# info-orbs.net
KiCad netlist of a schematic drawn in EasyEDA
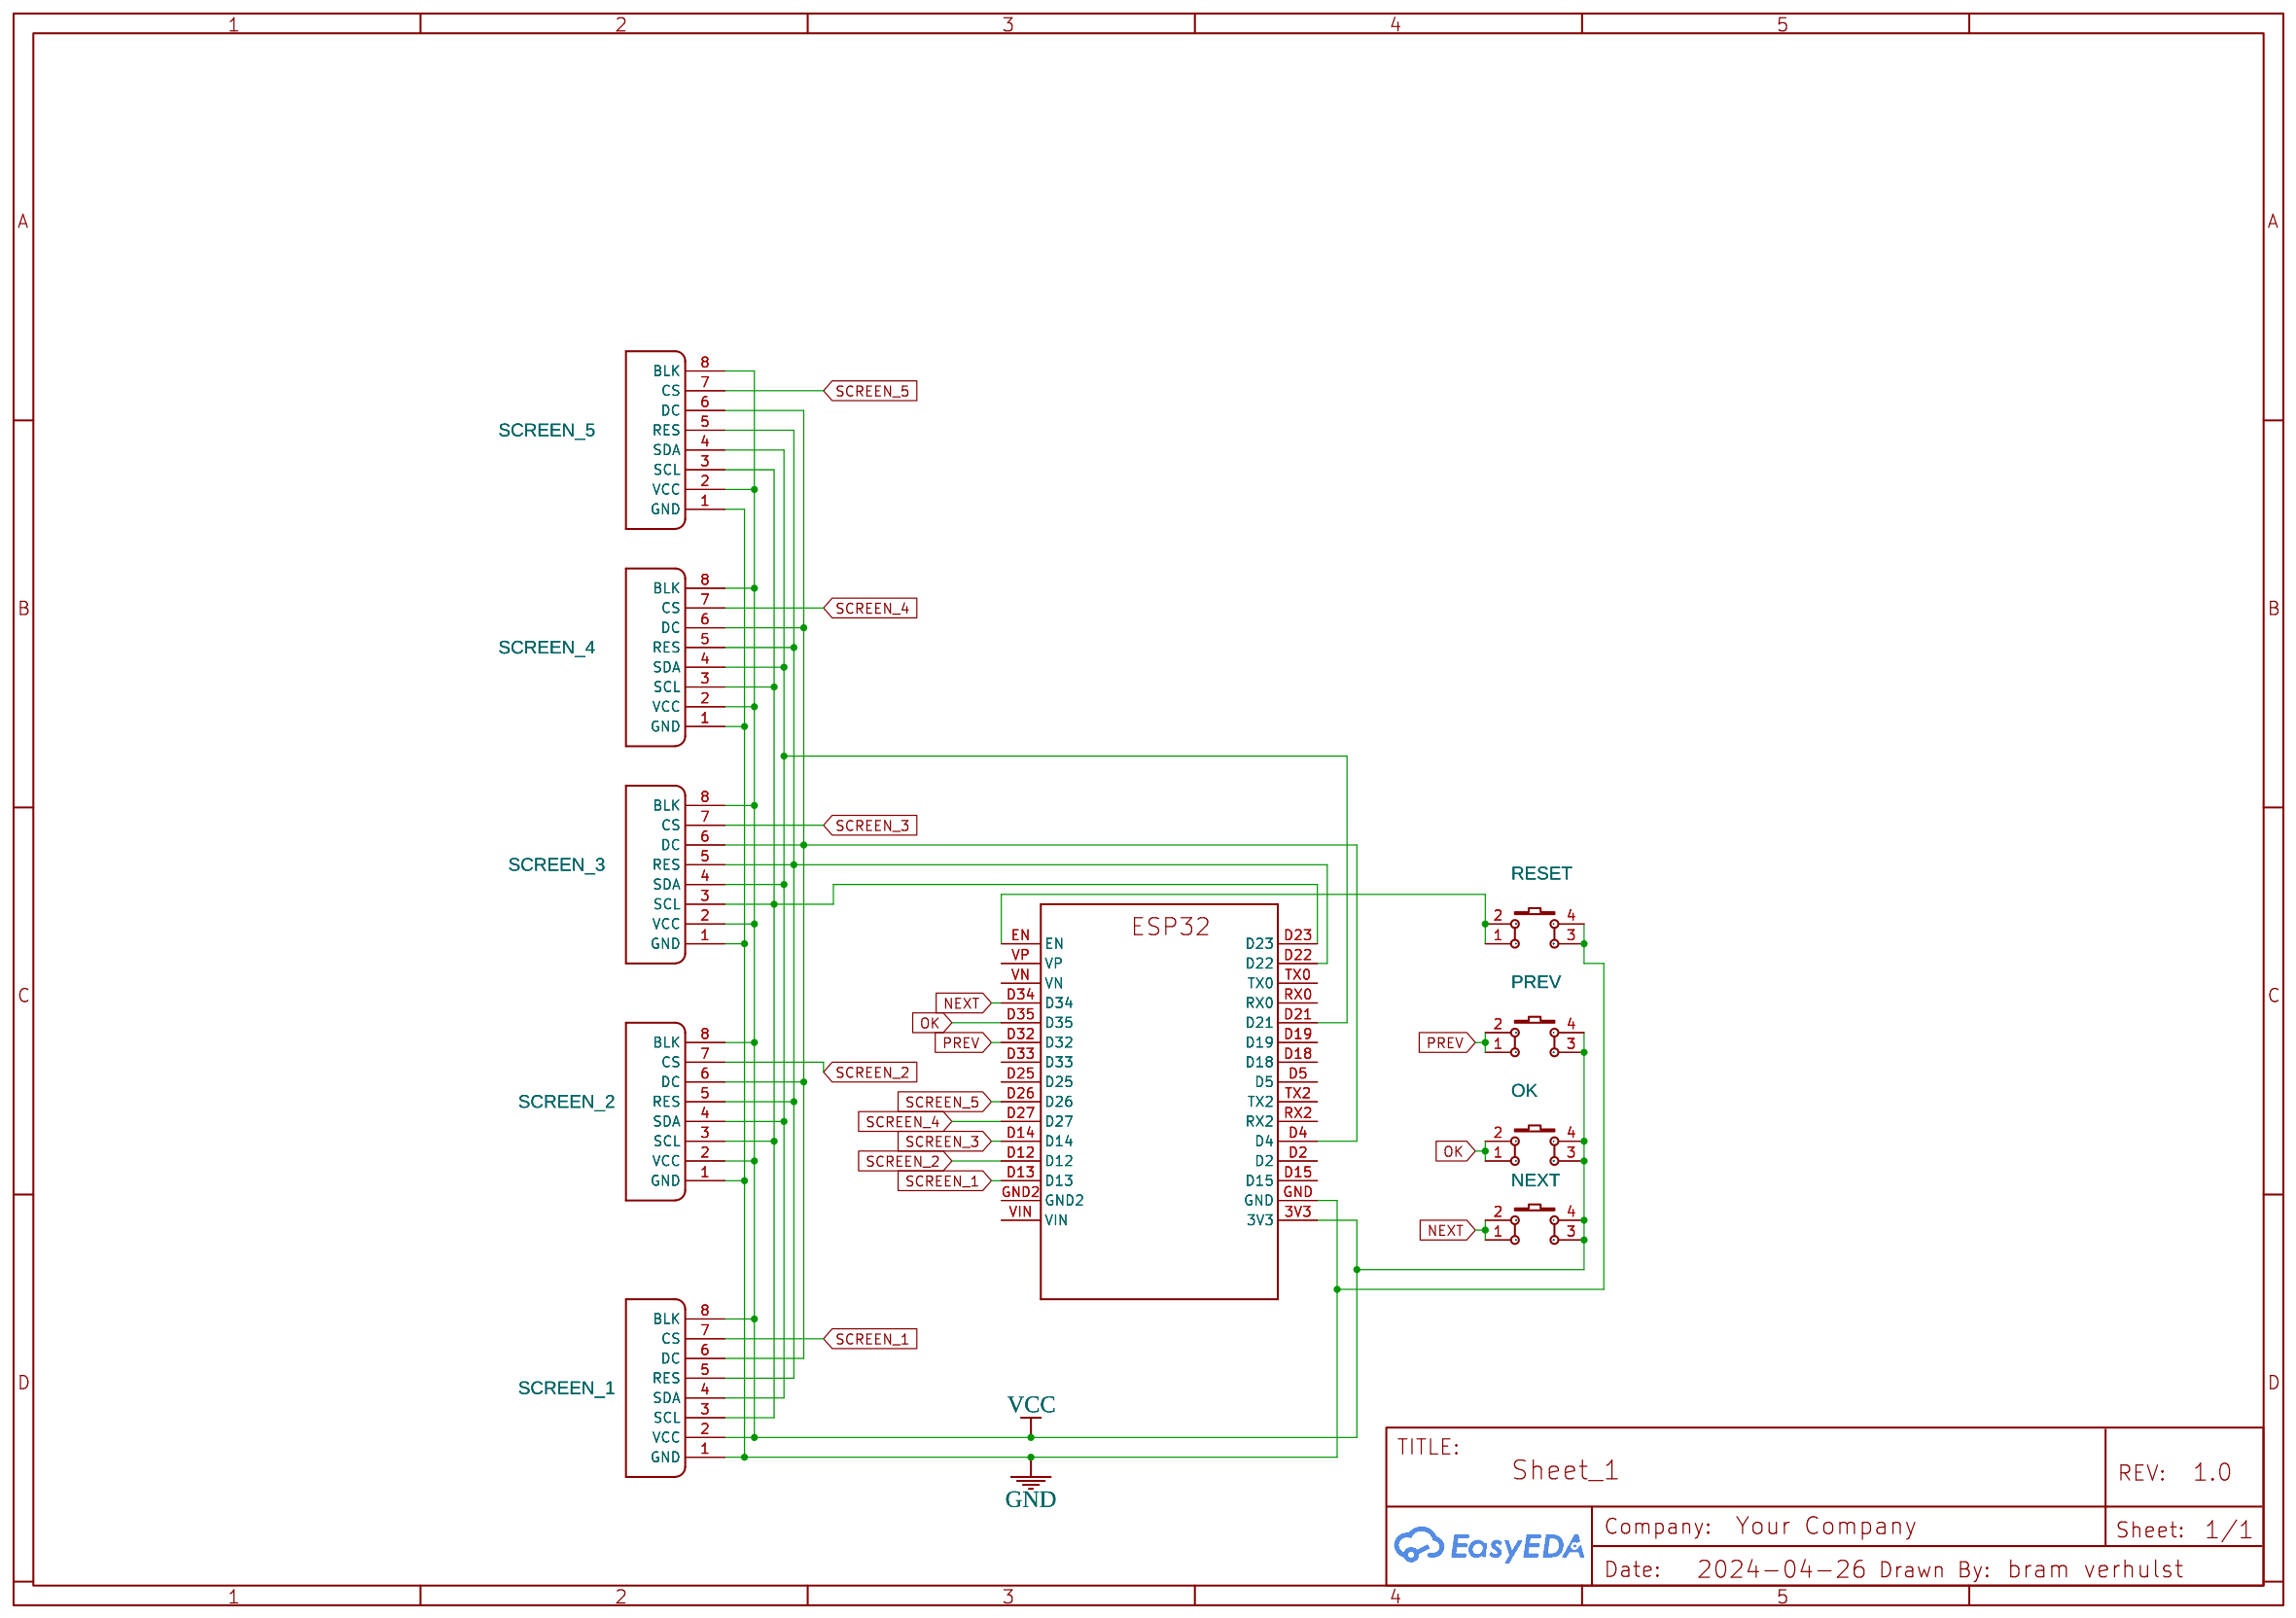
[diagram p0: schematic sheet]

(export (version "E")
  (design (tool "Eeschema 10.0.6"))
  (components
    (comp (ref "1")
      (value "ESP32-DEVKIT-V1-30PIN COPY 00.2 COPY")
      (libsource (lib "") (part "ESP32-DEVKIT-V1-30PIN"))
    )
    (comp (ref "NEXT")
      (value "K4-6×6_TH")
      (fields (field (name "Manufacturer Part") "K2-1102DP-E4SW-04") (field (name "Manufacturer") "韩国韩荣"))
      (libsource (lib "") (part "K4-6×6_TH"))
    )
    (comp (ref "OK")
      (value "K4-6×6_TH")
      (fields (field (name "Manufacturer Part") "K2-1102DP-E4SW-04") (field (name "Manufacturer") "韩国韩荣"))
      (libsource (lib "") (part "K4-6×6_TH_3"))
    )
    (comp (ref "PREV")
      (value "K4-6×6_TH")
      (fields (field (name "Manufacturer Part") "K2-1102DP-E4SW-04") (field (name "Manufacturer") "韩国韩荣"))
      (libsource (lib "") (part "K4-6×6_TH_1"))
    )
    (comp (ref "RESET")
      (value "K4-6×6_TH")
      (fields (field (name "Manufacturer Part") "K2-1102DP-E4SW-04") (field (name "Manufacturer") "韩国韩荣"))
      (libsource (lib "") (part "K4-6×6_TH_2"))
    )
    (comp (ref "SCREEN_1")
      (value "CHU-8 (DS1069-8 M) GC9A01A")
      (fields (field (name "Manufacturer Part") "DS1069"))
      (libsource (lib "") (part "CHU-8 (DS1069-8 M) GC9A01A"))
    )
    (comp (ref "SCREEN_2")
      (value "CHU-8 (DS1069-8 M) GC9A01A")
      (fields (field (name "Manufacturer Part") "DS1069"))
      (libsource (lib "") (part "CHU-8 (DS1069-8 M) GC9A01A"))
    )
    (comp (ref "SCREEN_3")
      (value "CHU-8 (DS1069-8 M) GC9A01A")
      (fields (field (name "Manufacturer Part") "DS1069"))
      (libsource (lib "") (part "CHU-8 (DS1069-8 M) GC9A01A"))
    )
    (comp (ref "SCREEN_4")
      (value "CHU-8 (DS1069-8 M) GC9A01A")
      (fields (field (name "Manufacturer Part") "DS1069"))
      (libsource (lib "") (part "CHU-8 (DS1069-8 M) GC9A01A"))
    )
    (comp (ref "SCREEN_5")
      (value "CHU-8 (DS1069-8 M) GC9A01A")
      (fields (field (name "Manufacturer Part") "DS1069"))
      (libsource (lib "") (part "CHU-8 (DS1069-8 M) GC9A01A"))
    )
  )
  (nets
    (net (code "1") (name "GND") (class "Default")
      (node (ref "1") (pin "GND") (pinfunction "GND_GND") (pintype "unspecified"))
      (node (ref "RESET") (pin "3") (pinfunction "3_3") (pintype "unspecified"))
      (node (ref "RESET") (pin "4") (pinfunction "4_4") (pintype "unspecified"))
      (node (ref "SCREEN_1") (pin "1") (pinfunction "GND_1") (pintype "unspecified"))
      (node (ref "SCREEN_2") (pin "1") (pinfunction "GND_1") (pintype "unspecified"))
      (node (ref "SCREEN_3") (pin "1") (pinfunction "GND_1") (pintype "unspecified"))
      (node (ref "SCREEN_4") (pin "1") (pinfunction "GND_1") (pintype "unspecified"))
      (node (ref "SCREEN_5") (pin "1") (pinfunction "GND_1") (pintype "unspecified"))
    )
    (net (code "2") (name "NEXT") (class "Default")
      (node (ref "1") (pin "D34") (pinfunction "D34_D34") (pintype "unspecified"))
      (node (ref "NEXT") (pin "1") (pinfunction "1_1") (pintype "unspecified"))
      (node (ref "NEXT") (pin "2") (pinfunction "2_2") (pintype "unspecified"))
    )
    (net (code "3") (name "Net-(1-PadEN)") (class "Default")
      (node (ref "1") (pin "EN") (pinfunction "EN_EN") (pintype "unspecified"))
      (node (ref "RESET") (pin "1") (pinfunction "1_1") (pintype "unspecified"))
      (node (ref "RESET") (pin "2") (pinfunction "2_2") (pintype "unspecified"))
    )
    (net (code "4") (name "Net-(SCREEN_1-DC)") (class "Default")
      (node (ref "1") (pin "D4") (pinfunction "D4_D4") (pintype "unspecified"))
      (node (ref "SCREEN_1") (pin "6") (pinfunction "DC_6") (pintype "unspecified"))
      (node (ref "SCREEN_2") (pin "6") (pinfunction "DC_6") (pintype "unspecified"))
      (node (ref "SCREEN_3") (pin "6") (pinfunction "DC_6") (pintype "unspecified"))
      (node (ref "SCREEN_4") (pin "6") (pinfunction "DC_6") (pintype "unspecified"))
      (node (ref "SCREEN_5") (pin "6") (pinfunction "DC_6") (pintype "unspecified"))
    )
    (net (code "5") (name "Net-(SCREEN_1-RES)") (class "Default")
      (node (ref "1") (pin "D22") (pinfunction "D22_D22") (pintype "unspecified"))
      (node (ref "SCREEN_1") (pin "5") (pinfunction "RES_5") (pintype "unspecified"))
      (node (ref "SCREEN_2") (pin "5") (pinfunction "RES_5") (pintype "unspecified"))
      (node (ref "SCREEN_3") (pin "5") (pinfunction "RES_5") (pintype "unspecified"))
      (node (ref "SCREEN_4") (pin "5") (pinfunction "RES_5") (pintype "unspecified"))
      (node (ref "SCREEN_5") (pin "5") (pinfunction "RES_5") (pintype "unspecified"))
    )
    (net (code "6") (name "Net-(SCREEN_1-SCL)") (class "Default")
      (node (ref "1") (pin "D23") (pinfunction "D23_D23") (pintype "unspecified"))
      (node (ref "SCREEN_1") (pin "3") (pinfunction "SCL_3") (pintype "unspecified"))
      (node (ref "SCREEN_2") (pin "3") (pinfunction "SCL_3") (pintype "unspecified"))
      (node (ref "SCREEN_3") (pin "3") (pinfunction "SCL_3") (pintype "unspecified"))
      (node (ref "SCREEN_4") (pin "3") (pinfunction "SCL_3") (pintype "unspecified"))
      (node (ref "SCREEN_5") (pin "3") (pinfunction "SCL_3") (pintype "unspecified"))
    )
    (net (code "7") (name "Net-(SCREEN_1-SDA)") (class "Default")
      (node (ref "1") (pin "D21") (pinfunction "D21_D21") (pintype "unspecified"))
      (node (ref "SCREEN_1") (pin "4") (pinfunction "SDA_4") (pintype "unspecified"))
      (node (ref "SCREEN_2") (pin "4") (pinfunction "SDA_4") (pintype "unspecified"))
      (node (ref "SCREEN_3") (pin "4") (pinfunction "SDA_4") (pintype "unspecified"))
      (node (ref "SCREEN_4") (pin "4") (pinfunction "SDA_4") (pintype "unspecified"))
      (node (ref "SCREEN_5") (pin "4") (pinfunction "SDA_4") (pintype "unspecified"))
    )
    (net (code "8") (name "OK") (class "Default")
      (node (ref "1") (pin "D35") (pinfunction "D35_D35") (pintype "unspecified"))
      (node (ref "OK") (pin "1") (pinfunction "1_1") (pintype "unspecified"))
      (node (ref "OK") (pin "2") (pinfunction "2_2") (pintype "unspecified"))
    )
    (net (code "9") (name "PREV") (class "Default")
      (node (ref "1") (pin "D32") (pinfunction "D32_D32") (pintype "unspecified"))
      (node (ref "PREV") (pin "1") (pinfunction "1_1") (pintype "unspecified"))
      (node (ref "PREV") (pin "2") (pinfunction "2_2") (pintype "unspecified"))
    )
    (net (code "10") (name "SCREEN_1") (class "Default")
      (node (ref "1") (pin "D13") (pinfunction "D13_D13") (pintype "unspecified"))
      (node (ref "SCREEN_1") (pin "7") (pinfunction "CS_7") (pintype "unspecified"))
    )
    (net (code "11") (name "SCREEN_2") (class "Default")
      (node (ref "1") (pin "D12") (pinfunction "D12_D12") (pintype "unspecified"))
      (node (ref "SCREEN_2") (pin "7") (pinfunction "CS_7") (pintype "unspecified"))
    )
    (net (code "12") (name "SCREEN_3") (class "Default")
      (node (ref "1") (pin "D14") (pinfunction "D14_D14") (pintype "unspecified"))
      (node (ref "SCREEN_3") (pin "7") (pinfunction "CS_7") (pintype "unspecified"))
    )
    (net (code "13") (name "SCREEN_4") (class "Default")
      (node (ref "1") (pin "D27") (pinfunction "D27_D27") (pintype "unspecified"))
      (node (ref "SCREEN_4") (pin "7") (pinfunction "CS_7") (pintype "unspecified"))
    )
    (net (code "14") (name "SCREEN_5") (class "Default")
      (node (ref "1") (pin "D26") (pinfunction "D26_D26") (pintype "unspecified"))
      (node (ref "SCREEN_5") (pin "7") (pinfunction "CS_7") (pintype "unspecified"))
    )
    (net (code "15") (name "VCC") (class "Default")
      (node (ref "1") (pin "3V3") (pinfunction "3V3_3V3") (pintype "unspecified"))
      (node (ref "NEXT") (pin "3") (pinfunction "3_3") (pintype "unspecified"))
      (node (ref "NEXT") (pin "4") (pinfunction "4_4") (pintype "unspecified"))
      (node (ref "OK") (pin "3") (pinfunction "3_3") (pintype "unspecified"))
      (node (ref "OK") (pin "4") (pinfunction "4_4") (pintype "unspecified"))
      (node (ref "PREV") (pin "3") (pinfunction "3_3") (pintype "unspecified"))
      (node (ref "PREV") (pin "4") (pinfunction "4_4") (pintype "unspecified"))
      (node (ref "SCREEN_1") (pin "2") (pinfunction "VCC_2") (pintype "unspecified"))
      (node (ref "SCREEN_1") (pin "8") (pinfunction "BLK_8") (pintype "unspecified"))
      (node (ref "SCREEN_2") (pin "2") (pinfunction "VCC_2") (pintype "unspecified"))
      (node (ref "SCREEN_2") (pin "8") (pinfunction "BLK_8") (pintype "unspecified"))
      (node (ref "SCREEN_3") (pin "2") (pinfunction "VCC_2") (pintype "unspecified"))
      (node (ref "SCREEN_3") (pin "8") (pinfunction "BLK_8") (pintype "unspecified"))
      (node (ref "SCREEN_4") (pin "2") (pinfunction "VCC_2") (pintype "unspecified"))
      (node (ref "SCREEN_4") (pin "8") (pinfunction "BLK_8") (pintype "unspecified"))
      (node (ref "SCREEN_5") (pin "2") (pinfunction "VCC_2") (pintype "unspecified"))
      (node (ref "SCREEN_5") (pin "8") (pinfunction "BLK_8") (pintype "unspecified"))
    )
    (net (code "16") (name "unconnected-(1-PadD2)") (class "Default")
      (node (ref "1") (pin "D2") (pinfunction "D2_D2") (pintype "unspecified"))
    )
    (net (code "17") (name "unconnected-(1-PadD5)") (class "Default")
      (node (ref "1") (pin "D5") (pinfunction "D5_D5") (pintype "unspecified"))
    )
    (net (code "18") (name "unconnected-(1-PadD15)") (class "Default")
      (node (ref "1") (pin "D15") (pinfunction "D15_D15") (pintype "unspecified"))
    )
    (net (code "19") (name "unconnected-(1-PadD18)") (class "Default")
      (node (ref "1") (pin "D18") (pinfunction "D18_D18") (pintype "unspecified"))
    )
    (net (code "20") (name "unconnected-(1-PadD19)") (class "Default")
      (node (ref "1") (pin "D19") (pinfunction "D19_D19") (pintype "unspecified"))
    )
    (net (code "21") (name "unconnected-(1-PadD25)") (class "Default")
      (node (ref "1") (pin "D25") (pinfunction "D25_D25") (pintype "unspecified"))
    )
    (net (code "22") (name "unconnected-(1-PadD33)") (class "Default")
      (node (ref "1") (pin "D33") (pinfunction "D33_D33") (pintype "unspecified"))
    )
    (net (code "23") (name "unconnected-(1-PadGND2)") (class "Default")
      (node (ref "1") (pin "GND2") (pinfunction "GND2_GND2") (pintype "unspecified"))
    )
    (net (code "24") (name "unconnected-(1-PadRX0)") (class "Default")
      (node (ref "1") (pin "RX0") (pinfunction "RX0_RX0") (pintype "unspecified"))
    )
    (net (code "25") (name "unconnected-(1-PadRX2)") (class "Default")
      (node (ref "1") (pin "RX2") (pinfunction "RX2_RX2") (pintype "unspecified"))
    )
    (net (code "26") (name "unconnected-(1-PadTX0)") (class "Default")
      (node (ref "1") (pin "TX0") (pinfunction "TX0_TX0") (pintype "unspecified"))
    )
    (net (code "27") (name "unconnected-(1-PadTX2)") (class "Default")
      (node (ref "1") (pin "TX2") (pinfunction "TX2_TX2") (pintype "unspecified"))
    )
    (net (code "28") (name "unconnected-(1-PadVIN)") (class "Default")
      (node (ref "1") (pin "VIN") (pinfunction "VIN_VIN") (pintype "unspecified"))
    )
    (net (code "29") (name "unconnected-(1-PadVN)") (class "Default")
      (node (ref "1") (pin "VN") (pinfunction "VN_VN") (pintype "unspecified"))
    )
    (net (code "30") (name "unconnected-(1-PadVP)") (class "Default")
      (node (ref "1") (pin "VP") (pinfunction "VP_VP") (pintype "unspecified"))
    )
  )
)
